# LPCB221_-_MLP_CHANNEL.net
KiCad netlist of a schematic drawn in Altium Designer
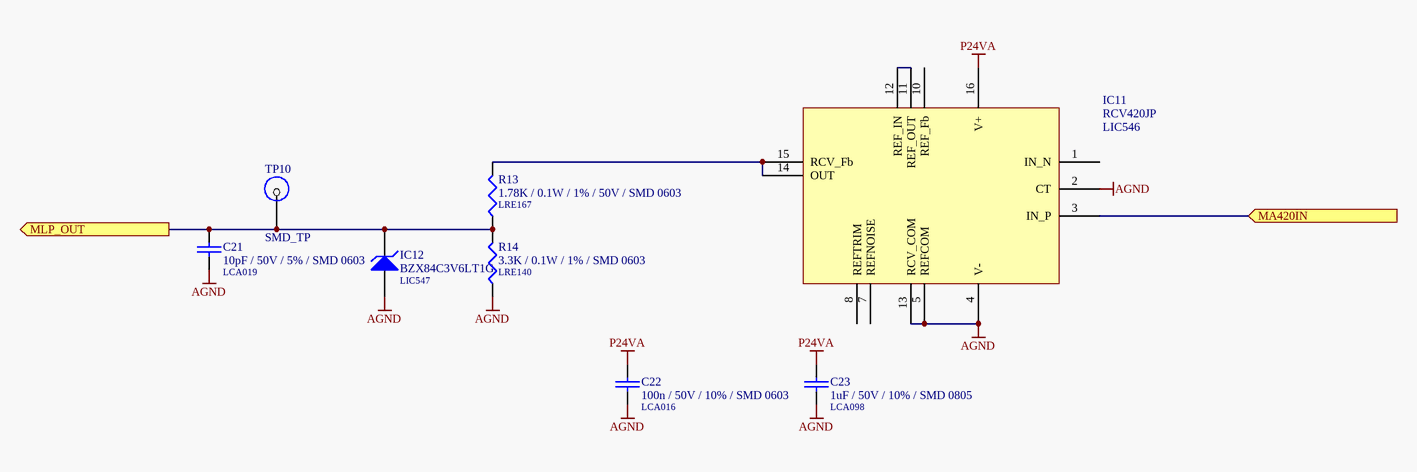
[diagram p0: LPCB221 - MLP CHANNEL.SchDoc]

(export (version "E")
  (design (tool "Eeschema 10.0.6"))
  (components
    (comp (ref "C21")
      (value "10pF / 50V / 5% / SMD 0603")
      (footprint "LFP011__CC1608-0603-IPC7351_B")
      (description "Capacitor, Ceramic Chip, 10pF, 50V, 5%, SMD 0603 [LCA019]")
      (fields (field (name "LDL_NUMBER") "LCA019"))
      (libsource (lib "LDL_Capacitors") (part "10pF / 50V / 5% / SMD 0603"))
    )
    (comp (ref "C22")
      (value "100n / 50V / 10% / SMD 0603")
      (footprint "LFP011__CC1608-0603-IPC7351_B")
      (description "Capacitor, Ceramic Chip, 100nF (0.1uF), 50V, 5%, SMD 0603 [LCA016]")
      (fields (field (name "LDL_NUMBER") "LCA016"))
      (libsource (lib "LDL_Capacitors") (part "100n / 50V / 10% / SMD 0603"))
    )
    (comp (ref "C23")
      (value "1uF / 50V / 10% / SMD 0805")
      (footprint "LFP010__CC2012-0805-IPC7351_B")
      (description "Capacitor, Ceramic Chip, 1uF, 50V, SMD 0805 [LCA098]")
      (fields (field (name "LDL_NUMBER") "LCA098"))
      (libsource (lib "LDL_Capacitors") (part "1uF / 50V / 10% / SMD 0805"))
    )
    (comp (ref "IC11")
      (value "RCV420JP")
      (footprint "DIP-P16/X1.5")
      (description "IC, 4-20mA Interface, DIP16 [LIC546]")
      (fields (field (name "LDL_NUMBER") "LIC546"))
      (libsource (lib "LDL_Semiconductors") (part "RCV420JP"))
    )
    (comp (ref "IC12")
      (value "BZX84C3V6LT1G")
      (footprint "LFP021__SOT23")
      (description "Diode, Zener, 3.6V, 0.225W, SMD [LIC083]")
      (fields (field (name "LDL_NUMBER") "LIC547"))
      (libsource (lib "LDL_Semiconductors") (part "BZX84C3V6LT1G"))
    )
    (comp (ref "R13")
      (value "1.78K / 0.1W / 1% / 50V / SMD 0603")
      (footprint "LFP020__CR1608-0603-IPC7351_B")
      (description "Resistor, Ceramic Chip, 1.78K, 0.1W, 1%, SMD 0603 [LRE167]")
      (fields (field (name "LDL_NUMBER") "LRE167"))
      (libsource (lib "LDL_Resistors") (part "1.78K / 0.1W / 1% / 50V / SMD 0603"))
    )
    (comp (ref "R14")
      (value "3.3K / 0.1W / 1% / SMD 0603")
      (footprint "LFP020__CR1608-0603-IPC7351_B")
      (description "Resistor, Ceramic Chip, 3.3K0, 0.1W, 1%, SMD 0603 [LRE140]")
      (fields (field (name "LDL_NUMBER") "LRE140"))
      (libsource (lib "LDL_Resistors") (part "3.3K / 0.1W / 1% / SMD 0603"))
    )
    (comp (ref "TP10")
      (value "SMD_TP")
      (footprint "SMD-TP")
      (description "SMD Test Point")
      (libsource (lib "LDL_Connectors") (part "SMD_TP"))
    )
  )
  (nets
    (net (code "1") (name "/MA420IN") (class "Default")
      (node (ref "IC11") (pin "3") (pinfunction "IN_P_3") (pintype "passive"))
    )
    (net (code "2") (name "/MLP_OUT") (class "Default")
      (node (ref "C21") (pin "1") (pintype "passive"))
      (node (ref "IC12") (pin "3") (pinfunction "K_3") (pintype "passive"))
      (node (ref "R13") (pin "1") (pintype "passive"))
      (node (ref "R14") (pin "2") (pintype "passive"))
      (node (ref "TP10") (pin "1") (pintype "passive"))
    )
    (net (code "3") (name "AGND") (class "Default")
      (node (ref "C21") (pin "2") (pintype "passive"))
      (node (ref "C22") (pin "2") (pintype "passive"))
      (node (ref "C23") (pin "2") (pintype "passive"))
      (node (ref "IC11") (pin "13") (pinfunction "RCV_COM_13") (pintype "passive"))
      (node (ref "IC11") (pin "2") (pinfunction "CT_2") (pintype "passive"))
      (node (ref "IC11") (pin "4") (pinfunction "V-_4") (pintype "power_in"))
      (node (ref "IC11") (pin "5") (pinfunction "REFCOM_5") (pintype "passive"))
      (node (ref "IC12") (pin "1") (pinfunction "A_1") (pintype "passive"))
      (node (ref "R14") (pin "1") (pintype "passive"))
    )
    (net (code "4") (name "Net-(IC11-OUT)") (class "Default")
      (node (ref "IC11") (pin "14") (pinfunction "OUT_14") (pintype "passive"))
      (node (ref "IC11") (pin "15") (pinfunction "RCV_Fb_15") (pintype "passive"))
      (node (ref "R13") (pin "2") (pintype "passive"))
    )
    (net (code "5") (name "Net-(IC11-REF_IN)") (class "Default")
      (node (ref "IC11") (pin "11") (pinfunction "REF_OUT_11") (pintype "passive"))
      (node (ref "IC11") (pin "12") (pinfunction "REF_IN_12") (pintype "passive"))
    )
    (net (code "6") (name "P24VA") (class "Default")
      (node (ref "C22") (pin "1") (pintype "passive"))
      (node (ref "C23") (pin "1") (pintype "passive"))
      (node (ref "IC11") (pin "16") (pinfunction "V+_16") (pintype "power_in"))
    )
    (net (code "7") (name "unconnected-(IC11-IN_N-Pad1)") (class "Default")
      (node (ref "IC11") (pin "1") (pinfunction "IN_N_1") (pintype "passive"))
    )
    (net (code "8") (name "unconnected-(IC11-REFNOISE-Pad7)") (class "Default")
      (node (ref "IC11") (pin "7") (pinfunction "REFNOISE_7") (pintype "passive"))
    )
    (net (code "9") (name "unconnected-(IC11-REFTRIM-Pad8)") (class "Default")
      (node (ref "IC11") (pin "8") (pinfunction "REFTRIM_8") (pintype "passive"))
    )
    (net (code "10") (name "unconnected-(IC11-REF_Fb-Pad10)") (class "Default")
      (node (ref "IC11") (pin "10") (pinfunction "REF_Fb_10") (pintype "passive"))
    )
  )
)
